# Inventor.net
KiCad netlist of a schematic drawn in EAGLE
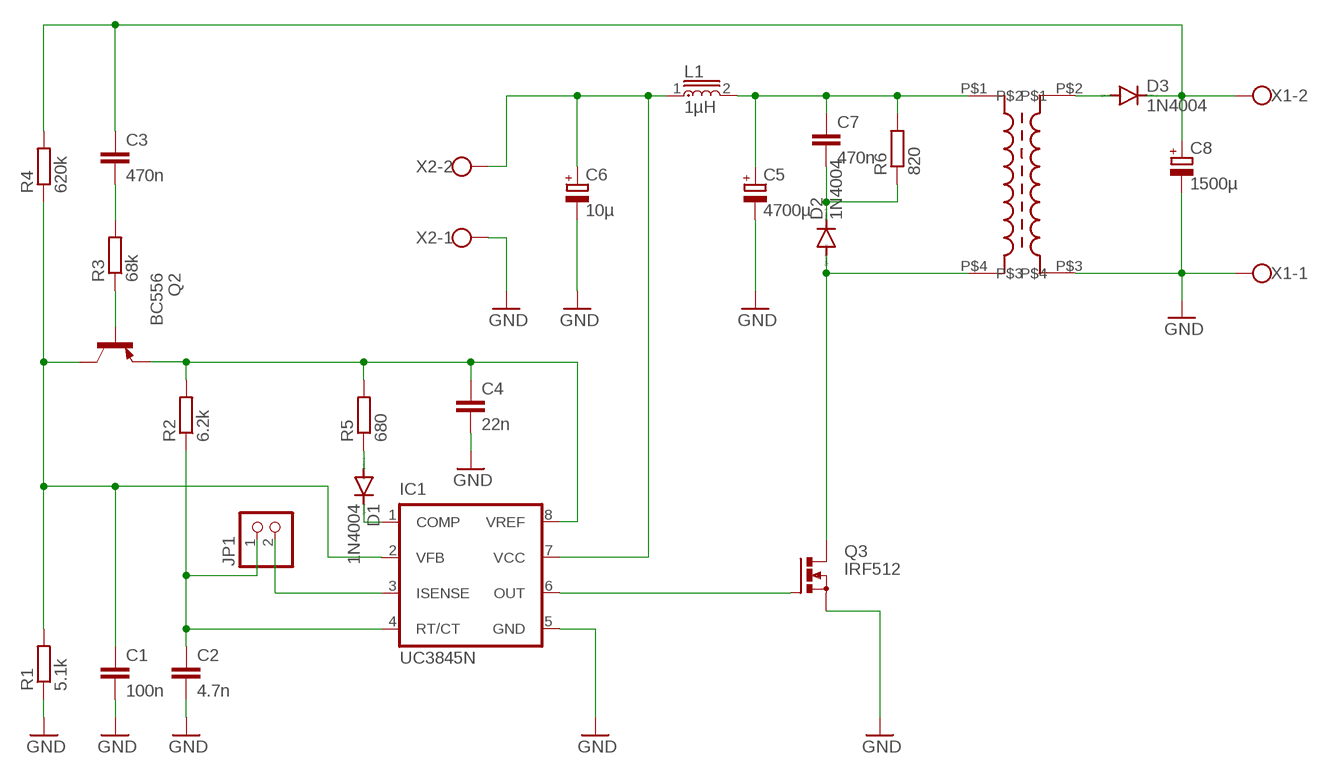
[diagram p0: schematic, sheet 1]

(export (version "E")
  (design (tool "Eeschema 10.0.6"))
  (components
    (comp (ref "C1")
      (value "100n")
      (footprint "eagle-import:C025-025X050")
      (libsource (lib "eagle-import") (part "C-EU025-025X050"))
    )
    (comp (ref "C2")
      (value "4.7n")
      (footprint "eagle-import:C025-025X050")
      (libsource (lib "eagle-import") (part "C-EU025-025X050"))
    )
    (comp (ref "C3")
      (value "470n")
      (footprint "eagle-import:C025-025X050")
      (libsource (lib "eagle-import") (part "C-EU025-025X050"))
    )
    (comp (ref "C4")
      (value "22n")
      (footprint "eagle-import:C025-025X050")
      (libsource (lib "eagle-import") (part "C-EU025-025X050"))
    )
    (comp (ref "C5")
      (value "4700µ")
      (footprint "eagle-import:E2,5-6")
      (libsource (lib "eagle-import") (part "CPOL-EUE2.5-6"))
    )
    (comp (ref "C6")
      (value "10µ")
      (footprint "eagle-import:E2,5-6")
      (libsource (lib "eagle-import") (part "CPOL-EUE2.5-6"))
    )
    (comp (ref "C7")
      (value "470n")
      (footprint "eagle-import:C025-025X050")
      (libsource (lib "eagle-import") (part "C-EU025-025X050"))
    )
    (comp (ref "C8")
      (value "1500µ")
      (footprint "eagle-import:E2,5-6")
      (libsource (lib "eagle-import") (part "CPOL-EUE2.5-6"))
    )
    (comp (ref "D1")
      (value "1N4004")
      (footprint "eagle-import:DO41-10")
      (libsource (lib "eagle-import") (part "1N4004"))
    )
    (comp (ref "D2")
      (value "1N4004")
      (footprint "eagle-import:DO41-10")
      (libsource (lib "eagle-import") (part "1N4004"))
    )
    (comp (ref "D3")
      (value "1N4004")
      (footprint "eagle-import:DO41-10")
      (libsource (lib "eagle-import") (part "1N4004"))
    )
    (comp (ref "IC1")
      (value "UC3845N")
      (footprint "eagle-import:DIL08")
      (libsource (lib "eagle-import") (part "UC384N5"))
    )
    (comp (ref "JP1")
      (value "PINHD-1X2")
      (footprint "eagle-import:1X02")
      (libsource (lib "eagle-import") (part "PINHD-1X2"))
    )
    (comp (ref "L1")
      (value "1µH")
      (footprint "eagle-import:P0762NL")
      (libsource (lib "eagle-import") (part "P0762.NL103"))
    )
    (comp (ref "Q2")
      (value "BC556")
      (footprint "eagle-import:TO92-EBC")
      (libsource (lib "eagle-import") (part "BC556"))
    )
    (comp (ref "Q3")
      (value "IRF512")
      (footprint "eagle-import:TO220BV")
      (libsource (lib "eagle-import") (part "IRF512"))
    )
    (comp (ref "R1")
      (value "5.1k")
      (footprint "eagle-import:0204_7")
      (libsource (lib "eagle-import") (part "R-EU_0204/7"))
    )
    (comp (ref "R2")
      (value "6.2k")
      (footprint "eagle-import:0204_7")
      (libsource (lib "eagle-import") (part "R-EU_0204/7"))
    )
    (comp (ref "R3")
      (value "68k")
      (footprint "eagle-import:0204_7")
      (libsource (lib "eagle-import") (part "R-EU_0204/7"))
    )
    (comp (ref "R4")
      (value "620k")
      (footprint "eagle-import:0204_7")
      (libsource (lib "eagle-import") (part "R-EU_0204/7"))
    )
    (comp (ref "R5")
      (value "680")
      (footprint "eagle-import:0204_7")
      (libsource (lib "eagle-import") (part "R-EU_0204/7"))
    )
    (comp (ref "R6")
      (value "820")
      (footprint "eagle-import:0204_7")
      (libsource (lib "eagle-import") (part "R-EU_0204/7"))
    )
    (comp (ref "U$1") (value "T2") (footprint "eagle-import:F2") (libsource (lib "eagle-import") (part "T2")))
    (comp (ref "X1")
      (value "W237-102")
      (footprint "eagle-import:W237-102")
      (fields (field (name "MPN") "237-102"))
      (libsource (lib "eagle-import") (part "W237-102"))
    )
    (comp (ref "X2")
      (value "W237-102")
      (footprint "eagle-import:W237-102")
      (fields (field (name "MPN") "237-102"))
      (libsource (lib "eagle-import") (part "W237-102"))
    )
  )
  (nets
    (net (code "1") (name "GND") (class "Default")
      (node (ref "C1") (pin "2") (pinfunction "2_2") (pintype "passive"))
      (node (ref "C2") (pin "2") (pinfunction "2_2") (pintype "passive"))
      (node (ref "C4") (pin "2") (pinfunction "2_2") (pintype "passive"))
      (node (ref "C5") (pin "-") (pinfunction "-_-") (pintype "passive"))
      (node (ref "C6") (pin "-") (pinfunction "-_-") (pintype "passive"))
      (node (ref "C8") (pin "-") (pinfunction "-_-") (pintype "passive"))
      (node (ref "IC1") (pin "5") (pinfunction "GND_5") (pintype "power_in"))
      (node (ref "Q3") (pin "S") (pinfunction "S_S") (pintype "passive"))
      (node (ref "R1") (pin "1") (pinfunction "1_1") (pintype "passive"))
      (node (ref "U$1") (pin "P$3") (pinfunction "P$3_P$3") (pintype "bidirectional"))
      (node (ref "X1") (pin "1") (pinfunction "KL_1") (pintype "passive"))
      (node (ref "X2") (pin "1") (pinfunction "KL_1") (pintype "passive"))
    )
    (net (code "2") (name "Net-(C3-Pad2)") (class "Default")
      (node (ref "C3") (pin "2") (pinfunction "2_2") (pintype "passive"))
      (node (ref "R3") (pin "2") (pinfunction "2_2") (pintype "passive"))
    )
    (net (code "3") (name "Net-(C5-Pad+)") (class "Default")
      (node (ref "C5") (pin "+") (pinfunction "+_+") (pintype "passive"))
      (node (ref "C7") (pin "1") (pinfunction "1_1") (pintype "passive"))
      (node (ref "L1") (pin "2") (pinfunction "2_2") (pintype "passive"))
      (node (ref "R6") (pin "2") (pinfunction "2_2") (pintype "passive"))
      (node (ref "U$1") (pin "P$1") (pinfunction "P$1_P$1") (pintype "bidirectional"))
    )
    (net (code "4") (name "Net-(C7-Pad2)") (class "Default")
      (node (ref "C7") (pin "2") (pinfunction "2_2") (pintype "passive"))
      (node (ref "D2") (pin "C") (pinfunction "C_C") (pintype "passive"))
      (node (ref "R6") (pin "1") (pinfunction "1_1") (pintype "passive"))
    )
    (net (code "5") (name "Net-(D1-PadA)") (class "Default")
      (node (ref "D1") (pin "A") (pinfunction "A_A") (pintype "passive"))
      (node (ref "R5") (pin "1") (pinfunction "1_1") (pintype "passive"))
    )
    (net (code "6") (name "Net-(D2-PadA)") (class "Default")
      (node (ref "D2") (pin "A") (pinfunction "A_A") (pintype "passive"))
      (node (ref "Q3") (pin "D") (pinfunction "D_D") (pintype "passive"))
      (node (ref "U$1") (pin "P$4") (pinfunction "P$4_P$4") (pintype "bidirectional"))
    )
    (net (code "7") (name "Net-(D3-PadA)") (class "Default")
      (node (ref "D3") (pin "A") (pinfunction "A_A") (pintype "passive"))
      (node (ref "U$1") (pin "P$2") (pinfunction "P$2_P$2") (pintype "bidirectional"))
    )
    (net (code "8") (name "Net-(IC1-COMP)") (class "Default")
      (node (ref "D1") (pin "C") (pinfunction "C_C") (pintype "passive"))
      (node (ref "IC1") (pin "1") (pinfunction "COMP_1") (pintype "passive"))
    )
    (net (code "9") (name "Net-(IC1-ISENSE)") (class "Default")
      (node (ref "IC1") (pin "3") (pinfunction "ISENSE_3") (pintype "input"))
      (node (ref "JP1") (pin "2") (pinfunction "2_2") (pintype "passive"))
    )
    (net (code "10") (name "Net-(IC1-OUT)") (class "Default")
      (node (ref "IC1") (pin "6") (pinfunction "OUT_6") (pintype "output"))
      (node (ref "Q3") (pin "G") (pinfunction "G_G") (pintype "passive"))
    )
    (net (code "11") (name "Net-(IC1-RT{slash}CT)") (class "Default")
      (node (ref "C2") (pin "1") (pinfunction "1_1") (pintype "passive"))
      (node (ref "IC1") (pin "4") (pinfunction "RT/CT_4") (pintype "passive"))
      (node (ref "JP1") (pin "1") (pinfunction "1_1") (pintype "passive"))
      (node (ref "R2") (pin "1") (pinfunction "1_1") (pintype "passive"))
    )
    (net (code "12") (name "Net-(IC1-VCC)") (class "Default")
      (node (ref "C6") (pin "+") (pinfunction "+_+") (pintype "passive"))
      (node (ref "IC1") (pin "7") (pinfunction "VCC_7") (pintype "power_in"))
      (node (ref "L1") (pin "1") (pinfunction "1_1") (pintype "passive"))
      (node (ref "X2") (pin "2") (pinfunction "KL_2") (pintype "passive"))
    )
    (net (code "13") (name "Net-(IC1-VFB)") (class "Default")
      (node (ref "C1") (pin "1") (pinfunction "1_1") (pintype "passive"))
      (node (ref "IC1") (pin "2") (pinfunction "VFB_2") (pintype "input"))
      (node (ref "Q2") (pin "C") (pinfunction "C_C") (pintype "passive"))
      (node (ref "R1") (pin "2") (pinfunction "2_2") (pintype "passive"))
      (node (ref "R4") (pin "1") (pinfunction "1_1") (pintype "passive"))
    )
    (net (code "14") (name "Net-(IC1-VREF)") (class "Default")
      (node (ref "C4") (pin "1") (pinfunction "1_1") (pintype "passive"))
      (node (ref "IC1") (pin "8") (pinfunction "VREF_8") (pintype "passive"))
      (node (ref "Q2") (pin "E") (pinfunction "E_E") (pintype "passive"))
      (node (ref "R2") (pin "2") (pinfunction "2_2") (pintype "passive"))
      (node (ref "R5") (pin "2") (pinfunction "2_2") (pintype "passive"))
    )
    (net (code "15") (name "Net-(Q2-PadB)") (class "Default")
      (node (ref "Q2") (pin "B") (pinfunction "B_B") (pintype "passive"))
      (node (ref "R3") (pin "1") (pinfunction "1_1") (pintype "passive"))
    )
    (net (code "16") (name "Net-(X1B-KL)") (class "Default")
      (node (ref "C3") (pin "1") (pinfunction "1_1") (pintype "passive"))
      (node (ref "C8") (pin "+") (pinfunction "+_+") (pintype "passive"))
      (node (ref "D3") (pin "C") (pinfunction "C_C") (pintype "passive"))
      (node (ref "R4") (pin "2") (pinfunction "2_2") (pintype "passive"))
      (node (ref "X1") (pin "2") (pinfunction "KL_2") (pintype "passive"))
    )
  )
)
